# 1_Schematic_schdoc.net
KiCad netlist of a schematic drawn in Altium Designer
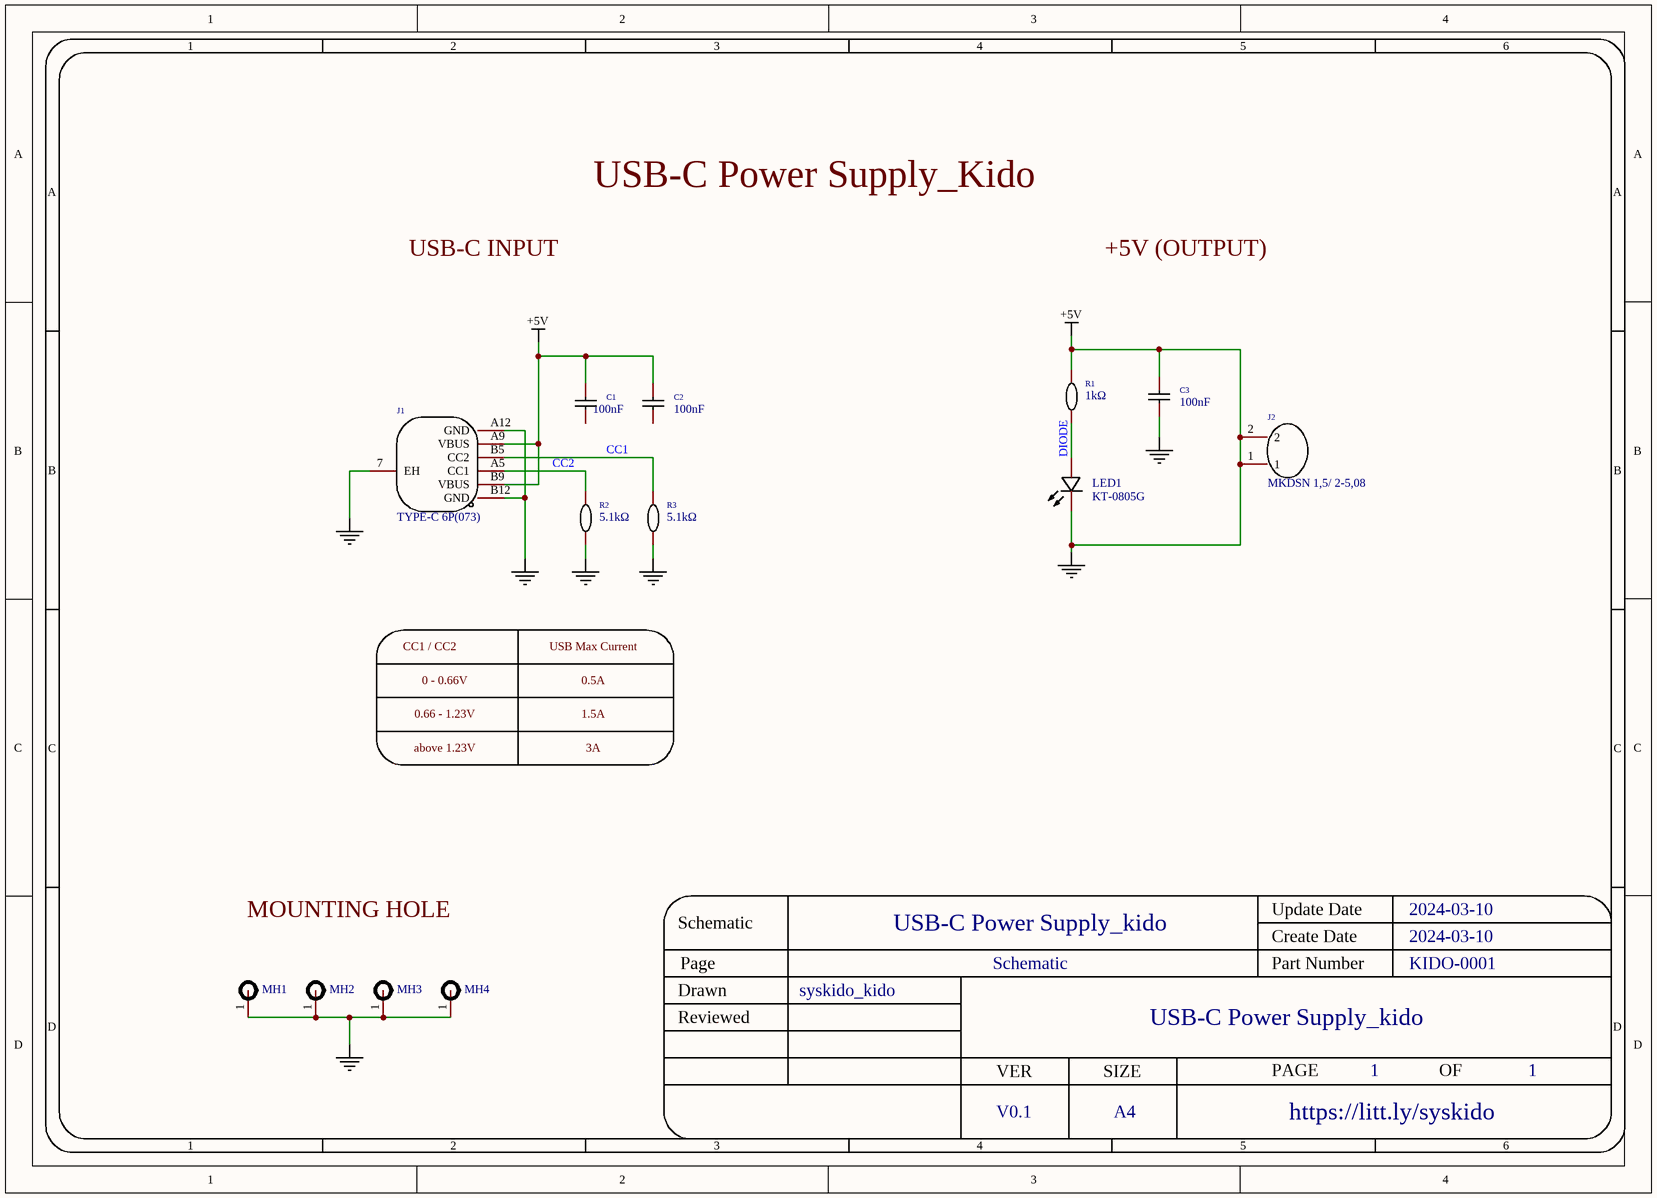
[diagram p0: 1_Schematic.schdoc.schdoc]

(export (version "E")
  (design (tool "Eeschema 10.0.6"))
  (components
    (comp (ref "C1")
      (value "100nF")
      (footprint "C0805")
      (fields
        (field (name "NAME") "100nF")
        (field (name "MANUFACTURER PART") "CC0805KRX7R9BB104")
        (field (name "MANUFACTURER") "YAGEO(国巨)")
        (field (name "TOLERANCE") "±10%")
      )
      (libsource (lib "altium-import") (part "root_1_CC0805KRX7R9BB104_"))
    )
    (comp (ref "C2")
      (value "100nF")
      (footprint "C0805")
      (fields
        (field (name "NAME") "100nF")
        (field (name "MANUFACTURER PART") "CC0805KRX7R9BB104")
        (field (name "MANUFACTURER") "YAGEO(国巨)")
        (field (name "TOLERANCE") "±10%")
      )
      (libsource (lib "altium-import") (part "root_1_CC0805KRX7R9BB104_"))
    )
    (comp (ref "C3")
      (value "100nF")
      (footprint "C0805")
      (fields
        (field (name "NAME") "100nF")
        (field (name "MANUFACTURER PART") "CC0805KRX7R9BB104")
        (field (name "MANUFACTURER") "YAGEO(国巨)")
        (field (name "TOLERANCE") "±10%")
      )
      (libsource (lib "altium-import") (part "root_1_CC0805KRX7R9BB104_"))
    )
    (comp (ref "J1")
      (value "TYPE-C 6P(073)")
      (footprint "TYPE-C-SMD_TYPE-C-6P")
      (fields (field (name "NAME") "TYPE-C 6P(073)") (field (name "MANUFACTURER") "SHOU HAN(首韩)"))
      (libsource (lib "altium-import") (part "root_2_TYPE-C 6P(073)_"))
    )
    (comp (ref "J2")
      (value "MKDSN 1,5/ 2-5,08")
      (footprint "CONN-TH_2P-P5.08_1729128")
      (fields (field (name "NAME") "MKDSN 1,5/ 2-5,08") (field (name "MANUFACTURER") "Phoenix Contact(菲尼克斯)"))
      (libsource (lib "altium-import") (part "root_2_mirrored_MKDSN 1,5/ 2-5,08_"))
    )
    (comp (ref "LED1")
      (value "KT-0805G")
      (footprint "LED0805-R-RD")
      (fields (field (name "NAME") "KT-0805G") (field (name "MANUFACTURER") "KENTO"))
      (libsource (lib "altium-import") (part "root_1_KT-0805G_"))
    )
    (comp (ref "MH1")
      (value "MH_7.5x2.7MM")
      (footprint "MH_7.5X2.7MM")
      (libsource (lib "altium-import") (part "root_1_MH_7.5x2.7MM_"))
    )
    (comp (ref "MH2")
      (value "MH_7.5x2.7MM")
      (footprint "MH_7.5X2.7MM")
      (libsource (lib "altium-import") (part "root_1_MH_7.5x2.7MM_"))
    )
    (comp (ref "MH3")
      (value "MH_7.5x2.7MM")
      (footprint "MH_7.5X2.7MM")
      (libsource (lib "altium-import") (part "root_1_MH_7.5x2.7MM_"))
    )
    (comp (ref "MH4")
      (value "MH_7.5x2.7MM")
      (footprint "MH_7.5X2.7MM")
      (libsource (lib "altium-import") (part "root_1_MH_7.5x2.7MM_"))
    )
    (comp (ref "R1")
      (value "1kΩ")
      (footprint "R0805")
      (fields
        (field (name "NAME") "1kΩ")
        (field (name "MANUFACTURER") "UNI-ROYAL(厚声)")
        (field (name "MANUFACTURER PART") "0805W8F1001T5E")
        (field (name "TOLERANCE") "±1%")
      )
      (libsource (lib "altium-import") (part "root_1_0805W8F1001T5E_"))
    )
    (comp (ref "R2")
      (value "5.1kΩ")
      (footprint "R0805")
      (fields
        (field (name "NAME") "5.1kΩ")
        (field (name "MANUFACTURER") "UNI-ROYAL(厚声)")
        (field (name "MANUFACTURER PART") "0805W8F5101T5E")
        (field (name "TOLERANCE") "±1%")
      )
      (libsource (lib "altium-import") (part "root_1_0805W8F5101T5E_"))
    )
    (comp (ref "R3")
      (value "5.1kΩ")
      (footprint "R0805")
      (fields
        (field (name "NAME") "5.1kΩ")
        (field (name "MANUFACTURER") "UNI-ROYAL(厚声)")
        (field (name "MANUFACTURER PART") "0805W8F5101T5E")
        (field (name "TOLERANCE") "±1%")
      )
      (libsource (lib "altium-import") (part "root_1_0805W8F5101T5E_"))
    )
  )
  (nets
    (net (code "1") (name "+5V") (class "Default")
      (node (ref "C1") (pin "2") (pinfunction "2_2") (pintype "passive"))
      (node (ref "C2") (pin "2") (pinfunction "2_2") (pintype "passive"))
      (node (ref "C3") (pin "2") (pinfunction "2_2") (pintype "passive"))
      (node (ref "J1") (pin "A9") (pinfunction "VBUS_A9") (pintype "passive"))
      (node (ref "J1") (pin "B9") (pinfunction "VBUS_B9") (pintype "passive"))
      (node (ref "J2") (pin "1") (pinfunction "1_1") (pintype "passive"))
      (node (ref "J2") (pin "2") (pinfunction "2_2") (pintype "passive"))
      (node (ref "LED1") (pin "2") (pinfunction "K_2") (pintype "passive"))
      (node (ref "R1") (pin "2") (pinfunction "2_2") (pintype "passive"))
    )
    (net (code "2") (name "/CC1") (class "Default")
      (node (ref "J1") (pin "B5") (pinfunction "CC2_B5") (pintype "passive"))
      (node (ref "R3") (pin "2") (pinfunction "2_2") (pintype "passive"))
    )
    (net (code "3") (name "/CC2") (class "Default")
      (node (ref "J1") (pin "A5") (pinfunction "CC1_A5") (pintype "passive"))
      (node (ref "R2") (pin "2") (pinfunction "2_2") (pintype "passive"))
    )
    (net (code "4") (name "/DIODE") (class "Default")
      (node (ref "LED1") (pin "1") (pinfunction "A_1") (pintype "passive"))
      (node (ref "R1") (pin "1") (pinfunction "1_1") (pintype "passive"))
    )
    (net (code "5") (name "GND") (class "Default")
      (node (ref "C3") (pin "1") (pinfunction "1_1") (pintype "passive"))
      (node (ref "J1") (pin "7") (pinfunction "EH_7") (pintype "passive"))
      (node (ref "J1") (pin "A12") (pinfunction "GND_A12") (pintype "passive"))
      (node (ref "J1") (pin "B12") (pinfunction "GND_B12") (pintype "passive"))
      (node (ref "MH1") (pin "1") (pinfunction "1_1") (pintype "passive"))
      (node (ref "MH2") (pin "1") (pinfunction "1_1") (pintype "passive"))
      (node (ref "MH3") (pin "1") (pinfunction "1_1") (pintype "passive"))
      (node (ref "MH4") (pin "1") (pinfunction "1_1") (pintype "passive"))
      (node (ref "R2") (pin "1") (pinfunction "1_1") (pintype "passive"))
      (node (ref "R3") (pin "1") (pinfunction "1_1") (pintype "passive"))
    )
    (net (code "6") (name "unconnected-(C1-Pad1)") (class "Default")
      (node (ref "C1") (pin "1") (pinfunction "1_1") (pintype "passive"))
    )
    (net (code "7") (name "unconnected-(C2-Pad1)") (class "Default")
      (node (ref "C2") (pin "1") (pinfunction "1_1") (pintype "passive"))
    )
  )
)
